# LNA.net
KiCad netlist of a schematic drawn in Altium Designer
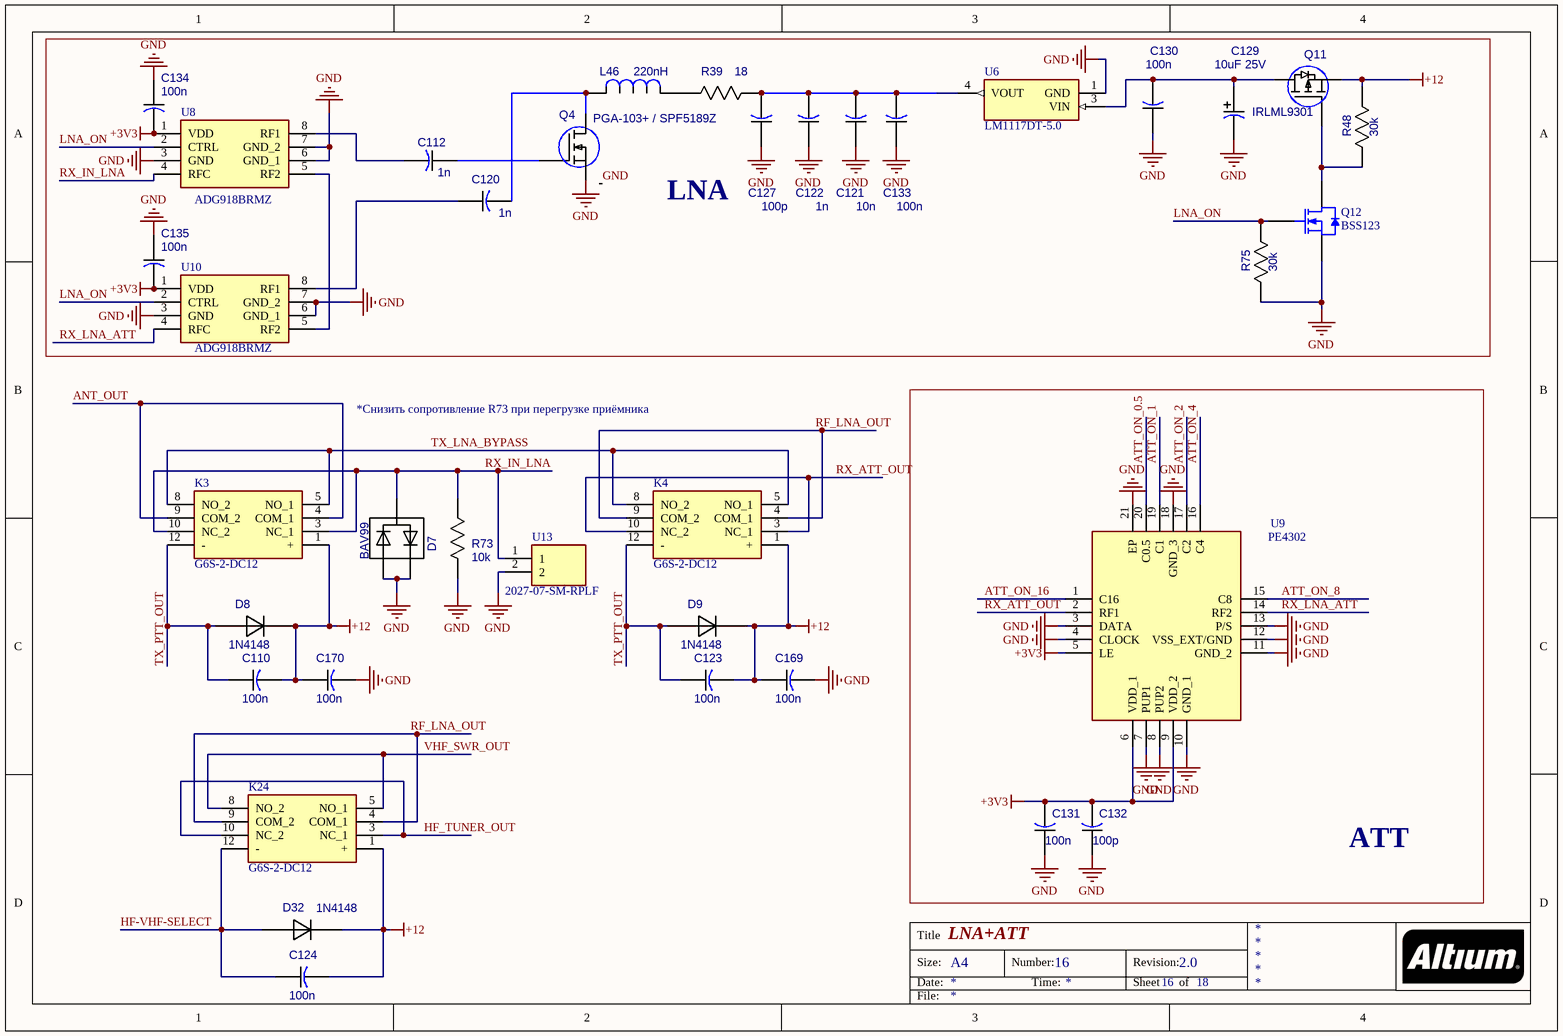
[diagram p0: LNA.SchDoc]

(export (version "E")
  (design (tool "Eeschema 10.0.6"))
  (components
    (comp (ref "C110")
      (value "100n")
      (footprint "CAP_0805")
      (description "CAP_0805")
      (libsource (lib "*") (part "CAP_0805"))
    )
    (comp (ref "C112")
      (value "1n")
      (footprint "CAP_0805")
      (description "CAP_0805")
      (libsource (lib "*") (part "CAP_0805"))
    )
    (comp (ref "C120")
      (value "1n")
      (footprint "CAP_0805")
      (description "CAP_0805")
      (libsource (lib "*") (part "CAP_0805"))
    )
    (comp (ref "C121")
      (value "10n")
      (footprint "6-0805_M")
      (description "CAP_0805")
      (libsource (lib "*") (part "CAP_0805"))
    )
    (comp (ref "C122")
      (value "1n")
      (footprint "6-0805_M")
      (description "CAP_0805")
      (libsource (lib "*") (part "CAP_0805"))
    )
    (comp (ref "C123")
      (value "100n")
      (footprint "CAP_0805")
      (description "CAP_0805")
      (libsource (lib "*") (part "CAP_0805"))
    )
    (comp (ref "C124")
      (value "100n")
      (footprint "CAP_0805")
      (description "CAP_0805")
      (libsource (lib "*") (part "CAP_0805"))
    )
    (comp (ref "C127")
      (value "100p")
      (footprint "6-0805_M")
      (description "CAP_0805")
      (libsource (lib "*") (part "CAP_0805"))
    )
    (comp (ref "C129")
      (value "10uF 25V")
      (footprint "CAPAE_5.3x5.3h6.1")
      (description "CAPAE_5.3x5.3h6.1")
      (libsource (lib "*") (part "CAPAE_5.3x5.3h6.1"))
    )
    (comp (ref "C130")
      (value "100n")
      (footprint "CAP_0805")
      (description "CAP_0805")
      (libsource (lib "") (part "CAP_0805_1"))
    )
    (comp (ref "C131")
      (value "100n")
      (footprint "6-0805_M")
      (description "CAP_0805")
      (libsource (lib "*") (part "CAP_0805"))
    )
    (comp (ref "C132")
      (value "100p")
      (footprint "6-0805_M")
      (description "CAP_0805")
      (libsource (lib "*") (part "CAP_0805"))
    )
    (comp (ref "C133")
      (value "100n")
      (footprint "CAP_0805")
      (description "CAP_0805")
      (libsource (lib "*") (part "CAP_0805"))
    )
    (comp (ref "C134")
      (value "100n")
      (footprint "CAP_0805")
      (description "CAP_0805")
      (libsource (lib "*") (part "CAP_0805"))
    )
    (comp (ref "C135")
      (value "100n")
      (footprint "CAP_0805")
      (description "CAP_0805")
      (libsource (lib "*") (part "CAP_0805"))
    )
    (comp (ref "C169")
      (value "100n")
      (footprint "CAP_0805")
      (description "CAP_0805")
      (libsource (lib "*") (part "CAP_0805"))
    )
    (comp (ref "C170")
      (value "100n")
      (footprint "CAP_0805")
      (description "CAP_0805")
      (libsource (lib "*") (part "CAP_0805"))
    )
    (comp (ref "D7") (value "BAV99") (footprint "SOT23") (libsource (lib "*") (part "BAV99")))
    (comp (ref "D8") (value "1N4148") (footprint "SS14") (libsource (lib "RF-UNIT-BIG") (part "1N4148")))
    (comp (ref "D9") (value "1N4148") (footprint "SS14") (libsource (lib "RF-UNIT-BIG") (part "1N4148")))
    (comp (ref "D32") (value "1N4148") (footprint "SS14") (libsource (lib "RF-UNIT-BIG") (part "1N4148")))
    (comp (ref "K3")
      (value "G6S-2-DC12")
      (footprint "SamacSys:G6S2DC12")
      (description "Relay or Contactor")
      (fields (field (name "MOUSER PART NUMBER") "653-G6S-2-DC12A"))
      (libsource (lib "*") (part "G6S-2-DC12"))
    )
    (comp (ref "K4")
      (value "G6S-2-DC12")
      (footprint "SamacSys:G6S2DC12")
      (description "Relay or Contactor")
      (fields (field (name "MOUSER PART NUMBER") "653-G6S-2-DC12A"))
      (libsource (lib "*") (part "G6S-2-DC12"))
    )
    (comp (ref "K24")
      (value "G6S-2-DC12")
      (footprint "SamacSys:G6S2DC12")
      (description "Relay or Contactor")
      (fields (field (name "MOUSER PART NUMBER") "653-G6S-2-DC12A"))
      (libsource (lib "*") (part "G6S-2-DC12"))
    )
    (comp (ref "L46")
      (value "220nH")
      (footprint "IND_1206")
      (description "IND_1206")
      (libsource (lib "*") (part "IND_1206"))
    )
    (comp (ref "Q4")
      (value "PGA-103+ / SPF5189Z")
      (footprint "SOT89")
      (libsource (lib "*") (part "PGA-103+"))
    )
    (comp (ref "Q11")
      (value "IRLML9301")
      (footprint "SOT23")
      (description "MOSFET")
      (libsource (lib "*") (part "MOSFET_ENH_PD"))
    )
    (comp (ref "Q12")
      (value "BSS123")
      (footprint "FAIR-SOT23-3_V")
      (fields (field (name "MANUFACTURER") "Fairchild"))
      (libsource (lib "Altium Content Vault") (part "NEMOS-GSD-3"))
    )
    (comp (ref "R39")
      (value "18")
      (footprint "RES_1206")
      (description "RES_1206")
      (libsource (lib "*") (part "RES_1206"))
    )
    (comp (ref "R48")
      (value "30k")
      (footprint "RES_0805")
      (description "RES_0805")
      (libsource (lib "*") (part "RES_0805"))
    )
    (comp (ref "R73")
      (value "10k")
      (footprint "RES_1206")
      (description "RES_1206")
      (libsource (lib "*") (part "RES_1206"))
    )
    (comp (ref "R75")
      (value "30k")
      (footprint "RES_0805")
      (description "RES_0805")
      (libsource (lib "*") (part "RES_0805"))
    )
    (comp (ref "U6")
      (value "LM1117DT-5.0")
      (footprint "SamacSys:TO228P991X238-3N")
      (description "Integrated Circuit")
      (fields
        (field (name "MANUFACTURER_PART_NUMBER") "LM1117DT-ADJ")
        (field (name "MOUSER PART NUMBER") "926-LM1117DT-ADJ")
      )
      (libsource (lib "*") (part "LM1117DT-ADJ"))
    )
    (comp (ref "U8")
      (value "ADG918BRMZ")
      (footprint "SOP65P490X110-8N")
      (description "Integrated Circuit")
      (fields (field (name "MOUSER PART NUMBER") "584-ADG918BRMZ") (field (name "RS PART NUMBER") "4969212P"))
      (libsource (lib "RF-UNIT-BIG") (part "ADG918BRMZ"))
    )
    (comp (ref "U9")
      (value "PE4302")
      (footprint "QFN50P400X400X90-21N")
      (description "Integrated Circuit")
      (fields (field (name "MANUFACTURER_PART_NUMBER") "PE4312C-Z"))
      (libsource (lib "RF-UNIT-BIG") (part "PE4312C-Z"))
    )
    (comp (ref "U10")
      (value "ADG918BRMZ")
      (footprint "SOP65P490X110-8N")
      (description "Integrated Circuit")
      (fields (field (name "MOUSER PART NUMBER") "584-ADG918BRMZ") (field (name "RS PART NUMBER") "4969212P"))
      (libsource (lib "RF-UNIT-BIG") (part "ADG918BRMZ"))
    )
    (comp (ref "U13")
      (value "2027-07-SM-RPLF")
      (footprint "SamacSys:200307SMRPLF")
      (description "Undefined or Miscellaneous")
      (fields
        (field (name "MANUFACTURER_PART_NUMBER") "2003-07-SM-RPLF")
        (field (name "MOUSER PART NUMBER") "652-2003-07-SM-RPLF")
      )
      (libsource (lib "*") (part "2003-07-SM-RPLF"))
    )
  )
  (nets
    (net (code "1") (name "+3V3") (class "Default")
      (node (ref "C131") (pin "2") (pinfunction "2_2") (pintype "passive"))
      (node (ref "C132") (pin "2") (pinfunction "2_2") (pintype "passive"))
      (node (ref "C134") (pin "2") (pinfunction "2_2") (pintype "passive"))
      (node (ref "C135") (pin "2") (pinfunction "2_2") (pintype "passive"))
      (node (ref "U10") (pin "1") (pinfunction "VDD_1") (pintype "power_in"))
      (node (ref "U8") (pin "1") (pinfunction "VDD_1") (pintype "power_in"))
      (node (ref "U9") (pin "5") (pinfunction "LE_5") (pintype "passive"))
      (node (ref "U9") (pin "6") (pinfunction "VDD_1_6") (pintype "passive"))
      (node (ref "U9") (pin "9") (pinfunction "VDD_2_9") (pintype "passive"))
    )
    (net (code "2") (name "+12") (class "Default")
      (node (ref "C110") (pin "2") (pinfunction "2_2") (pintype "passive"))
      (node (ref "C123") (pin "2") (pinfunction "2_2") (pintype "passive"))
      (node (ref "C124") (pin "2") (pinfunction "2_2") (pintype "passive"))
      (node (ref "C169") (pin "1") (pinfunction "1_1") (pintype "passive"))
      (node (ref "C170") (pin "1") (pinfunction "1_1") (pintype "passive"))
      (node (ref "D32") (pin "1") (pinfunction "K_1") (pintype "passive"))
      (node (ref "D8") (pin "1") (pinfunction "K_1") (pintype "passive"))
      (node (ref "D9") (pin "1") (pinfunction "K_1") (pintype "passive"))
      (node (ref "K24") (pin "1") (pinfunction "+_1") (pintype "passive"))
      (node (ref "K3") (pin "1") (pinfunction "+_1") (pintype "passive"))
      (node (ref "K4") (pin "1") (pinfunction "+_1") (pintype "passive"))
      (node (ref "Q11") (pin "2") (pinfunction "S_2") (pintype "passive"))
      (node (ref "R48") (pin "2") (pinfunction "2_2") (pintype "passive"))
    )
    (net (code "3") (name "/ANT_OUT") (class "Default")
      (node (ref "K3") (pin "4") (pinfunction "COM_1_4") (pintype "passive"))
      (node (ref "K3") (pin "9") (pinfunction "COM_2_9") (pintype "passive"))
    )
    (net (code "4") (name "/ATT_ON_0.5") (class "Default")
      (node (ref "U9") (pin "20") (pinfunction "C0.5_20") (pintype "passive"))
    )
    (net (code "5") (name "/ATT_ON_1") (class "Default")
      (node (ref "U9") (pin "19") (pinfunction "C1_19") (pintype "passive"))
    )
    (net (code "6") (name "/ATT_ON_2") (class "Default")
      (node (ref "U9") (pin "17") (pinfunction "C2_17") (pintype "passive"))
    )
    (net (code "7") (name "/ATT_ON_4") (class "Default")
      (node (ref "U9") (pin "16") (pinfunction "C4_16") (pintype "passive"))
    )
    (net (code "8") (name "/ATT_ON_8") (class "Default")
      (node (ref "U9") (pin "15") (pinfunction "C8_15") (pintype "passive"))
    )
    (net (code "9") (name "/ATT_ON_16") (class "Default")
      (node (ref "U9") (pin "1") (pinfunction "C16_1") (pintype "passive"))
    )
    (net (code "10") (name "/HF-VHF-SELECT") (class "Default")
      (node (ref "C124") (pin "1") (pinfunction "1_1") (pintype "passive"))
      (node (ref "D32") (pin "2") (pinfunction "A_2") (pintype "passive"))
      (node (ref "K24") (pin "12") (pinfunction "-_12") (pintype "passive"))
    )
    (net (code "11") (name "/HF_TUNER_OUT") (class "Default")
      (node (ref "K24") (pin "10") (pinfunction "NC_2_10") (pintype "passive"))
      (node (ref "K24") (pin "3") (pinfunction "NC_1_3") (pintype "passive"))
    )
    (net (code "12") (name "/LNA_ON") (class "Default")
      (node (ref "Q12") (pin "1") (pinfunction "G_1") (pintype "passive"))
      (node (ref "R75") (pin "2") (pinfunction "2_2") (pintype "passive"))
      (node (ref "U10") (pin "2") (pinfunction "CTRL_2") (pintype "passive"))
      (node (ref "U8") (pin "2") (pinfunction "CTRL_2") (pintype "passive"))
    )
    (net (code "13") (name "/RF_LNA_OUT") (class "Default")
      (node (ref "K24") (pin "4") (pinfunction "COM_1_4") (pintype "passive"))
      (node (ref "K24") (pin "9") (pinfunction "COM_2_9") (pintype "passive"))
      (node (ref "K4") (pin "4") (pinfunction "COM_1_4") (pintype "passive"))
      (node (ref "K4") (pin "9") (pinfunction "COM_2_9") (pintype "passive"))
    )
    (net (code "14") (name "/RX_ATT_OUT") (class "Default")
      (node (ref "K4") (pin "10") (pinfunction "NC_2_10") (pintype "passive"))
      (node (ref "K4") (pin "3") (pinfunction "NC_1_3") (pintype "passive"))
      (node (ref "U9") (pin "2") (pinfunction "RF1_2") (pintype "passive"))
    )
    (net (code "15") (name "/RX_IN_LNA") (class "Default")
      (node (ref "D7") (pin "3") (pinfunction "C(D1),A(D2)_3") (pintype "passive"))
      (node (ref "K3") (pin "10") (pinfunction "NC_2_10") (pintype "passive"))
      (node (ref "K3") (pin "3") (pinfunction "NC_1_3") (pintype "passive"))
      (node (ref "R73") (pin "2") (pinfunction "2_2") (pintype "passive"))
      (node (ref "U13") (pin "1") (pinfunction "1_1") (pintype "passive"))
      (node (ref "U8") (pin "4") (pinfunction "RFC_4") (pintype "passive"))
    )
    (net (code "16") (name "/RX_LNA_ATT") (class "Default")
      (node (ref "U10") (pin "4") (pinfunction "RFC_4") (pintype "passive"))
      (node (ref "U9") (pin "14") (pinfunction "RF2_14") (pintype "passive"))
    )
    (net (code "17") (name "/TX_LNA_BYPASS") (class "Default")
      (node (ref "K3") (pin "5") (pinfunction "NO_1_5") (pintype "passive"))
      (node (ref "K3") (pin "8") (pinfunction "NO_2_8") (pintype "passive"))
      (node (ref "K4") (pin "5") (pinfunction "NO_1_5") (pintype "passive"))
      (node (ref "K4") (pin "8") (pinfunction "NO_2_8") (pintype "passive"))
    )
    (net (code "18") (name "/TX_PTT_OUT") (class "Default")
      (node (ref "C110") (pin "1") (pinfunction "1_1") (pintype "passive"))
      (node (ref "C123") (pin "1") (pinfunction "1_1") (pintype "passive"))
      (node (ref "D8") (pin "2") (pinfunction "A_2") (pintype "passive"))
      (node (ref "D9") (pin "2") (pinfunction "A_2") (pintype "passive"))
      (node (ref "K3") (pin "12") (pinfunction "-_12") (pintype "passive"))
      (node (ref "K4") (pin "12") (pinfunction "-_12") (pintype "passive"))
    )
    (net (code "19") (name "/VHF_SWR_OUT") (class "Default")
      (node (ref "K24") (pin "5") (pinfunction "NO_1_5") (pintype "passive"))
      (node (ref "K24") (pin "8") (pinfunction "NO_2_8") (pintype "passive"))
    )
    (net (code "20") (name "GND") (class "Default")
      (node (ref "C121") (pin "1") (pinfunction "1_1") (pintype "passive"))
      (node (ref "C122") (pin "1") (pinfunction "1_1") (pintype "passive"))
      (node (ref "C127") (pin "1") (pinfunction "1_1") (pintype "passive"))
      (node (ref "C129") (pin "2") (pinfunction "MINUS_2") (pintype "passive"))
      (node (ref "C130") (pin "1") (pinfunction "1_1") (pintype "passive"))
      (node (ref "C131") (pin "1") (pinfunction "1_1") (pintype "passive"))
      (node (ref "C132") (pin "1") (pinfunction "1_1") (pintype "passive"))
      (node (ref "C133") (pin "1") (pinfunction "1_1") (pintype "passive"))
      (node (ref "C134") (pin "1") (pinfunction "1_1") (pintype "passive"))
      (node (ref "C135") (pin "1") (pinfunction "1_1") (pintype "passive"))
      (node (ref "C169") (pin "2") (pinfunction "2_2") (pintype "passive"))
      (node (ref "C170") (pin "2") (pinfunction "2_2") (pintype "passive"))
      (node (ref "D7") (pin "1") (pinfunction "A(D1)_1") (pintype "passive"))
      (node (ref "D7") (pin "2") (pinfunction "C(D2)_2") (pintype "passive"))
      (node (ref "Q12") (pin "2") (pinfunction "S_2") (pintype "passive"))
      (node (ref "Q4") (pin "0") (pinfunction "0_0") (pintype "passive"))
      (node (ref "Q4") (pin "2") (pinfunction "S_2") (pintype "passive"))
      (node (ref "R73") (pin "1") (pinfunction "1_1") (pintype "passive"))
      (node (ref "R75") (pin "1") (pinfunction "1_1") (pintype "passive"))
      (node (ref "U10") (pin "3") (pinfunction "GND_3") (pintype "power_in"))
      (node (ref "U10") (pin "6") (pinfunction "GND_1_6") (pintype "power_in"))
      (node (ref "U10") (pin "7") (pinfunction "GND_2_7") (pintype "power_in"))
      (node (ref "U13") (pin "2") (pinfunction "2_2") (pintype "passive"))
      (node (ref "U6") (pin "1") (pinfunction "GND_1") (pintype "passive"))
      (node (ref "U8") (pin "3") (pinfunction "GND_3") (pintype "power_in"))
      (node (ref "U8") (pin "6") (pinfunction "GND_1_6") (pintype "power_in"))
      (node (ref "U8") (pin "7") (pinfunction "GND_2_7") (pintype "power_in"))
      (node (ref "U9") (pin "10") (pinfunction "GND_1_10") (pintype "passive"))
      (node (ref "U9") (pin "11") (pinfunction "GND_2_11") (pintype "passive"))
      (node (ref "U9") (pin "12") (pinfunction "VSS_EXT/GND_12") (pintype "passive"))
      (node (ref "U9") (pin "13") (pinfunction "P/S_13") (pintype "passive"))
      (node (ref "U9") (pin "18") (pinfunction "GND_3_18") (pintype "passive"))
      (node (ref "U9") (pin "21") (pinfunction "EP_21") (pintype "passive"))
      (node (ref "U9") (pin "3") (pinfunction "DATA_3") (pintype "passive"))
      (node (ref "U9") (pin "4") (pinfunction "CLOCK_4") (pintype "passive"))
      (node (ref "U9") (pin "7") (pinfunction "PUP1_7") (pintype "passive"))
      (node (ref "U9") (pin "8") (pinfunction "PUP2_8") (pintype "passive"))
    )
    (net (code "21") (name "Net-(C129-PLUS)") (class "Default")
      (node (ref "C129") (pin "1") (pinfunction "PLUS_1") (pintype "passive"))
      (node (ref "C130") (pin "2") (pinfunction "2_2") (pintype "passive"))
      (node (ref "Q11") (pin "3") (pinfunction "D_3") (pintype "passive"))
      (node (ref "U6") (pin "3") (pinfunction "VIN_3") (pintype "input"))
    )
    (net (code "22") (name "Net-(L46-1)") (class "Default")
      (node (ref "C120") (pin "2") (pinfunction "2_2") (pintype "passive"))
      (node (ref "L46") (pin "2") (pinfunction "1_2") (pintype "passive"))
      (node (ref "Q4") (pin "3") (pinfunction "D_3") (pintype "passive"))
    )
    (net (code "23") (name "Net-(L46-2)") (class "Default")
      (node (ref "L46") (pin "1") (pinfunction "2_1") (pintype "passive"))
      (node (ref "R39") (pin "2") (pinfunction "2_2") (pintype "passive"))
    )
    (net (code "24") (name "Net-(Q4-G)") (class "Default")
      (node (ref "C112") (pin "1") (pinfunction "1_1") (pintype "passive"))
      (node (ref "Q4") (pin "1") (pinfunction "G_1") (pintype "passive"))
    )
    (net (code "25") (name "Net-(Q11-G)") (class "Default")
      (node (ref "Q11") (pin "1") (pinfunction "G_1") (pintype "passive"))
      (node (ref "Q12") (pin "3") (pinfunction "D_3") (pintype "passive"))
      (node (ref "R48") (pin "1") (pinfunction "1_1") (pintype "passive"))
    )
    (net (code "26") (name "Net-(U6-VOUT)") (class "Default")
      (node (ref "C121") (pin "2") (pinfunction "2_2") (pintype "passive"))
      (node (ref "C122") (pin "2") (pinfunction "2_2") (pintype "passive"))
      (node (ref "C127") (pin "2") (pinfunction "2_2") (pintype "passive"))
      (node (ref "C133") (pin "2") (pinfunction "2_2") (pintype "passive"))
      (node (ref "R39") (pin "1") (pinfunction "1_1") (pintype "passive"))
      (node (ref "U6") (pin "4") (pinfunction "VOUT_4") (pintype "output"))
    )
    (net (code "27") (name "Net-(U8-RF1)") (class "Default")
      (node (ref "C112") (pin "2") (pinfunction "2_2") (pintype "passive"))
      (node (ref "U8") (pin "8") (pinfunction "RF1_8") (pintype "passive"))
    )
    (net (code "28") (name "Net-(U10-RF1)") (class "Default")
      (node (ref "C120") (pin "1") (pinfunction "1_1") (pintype "passive"))
      (node (ref "U10") (pin "8") (pinfunction "RF1_8") (pintype "passive"))
    )
    (net (code "29") (name "Net-(U10-RF2)") (class "Default")
      (node (ref "U10") (pin "5") (pinfunction "RF2_5") (pintype "passive"))
      (node (ref "U8") (pin "5") (pinfunction "RF2_5") (pintype "passive"))
    )
  )
)
